# bbb_localization_cape.net
KiCad netlist of a schematic drawn in EAGLE
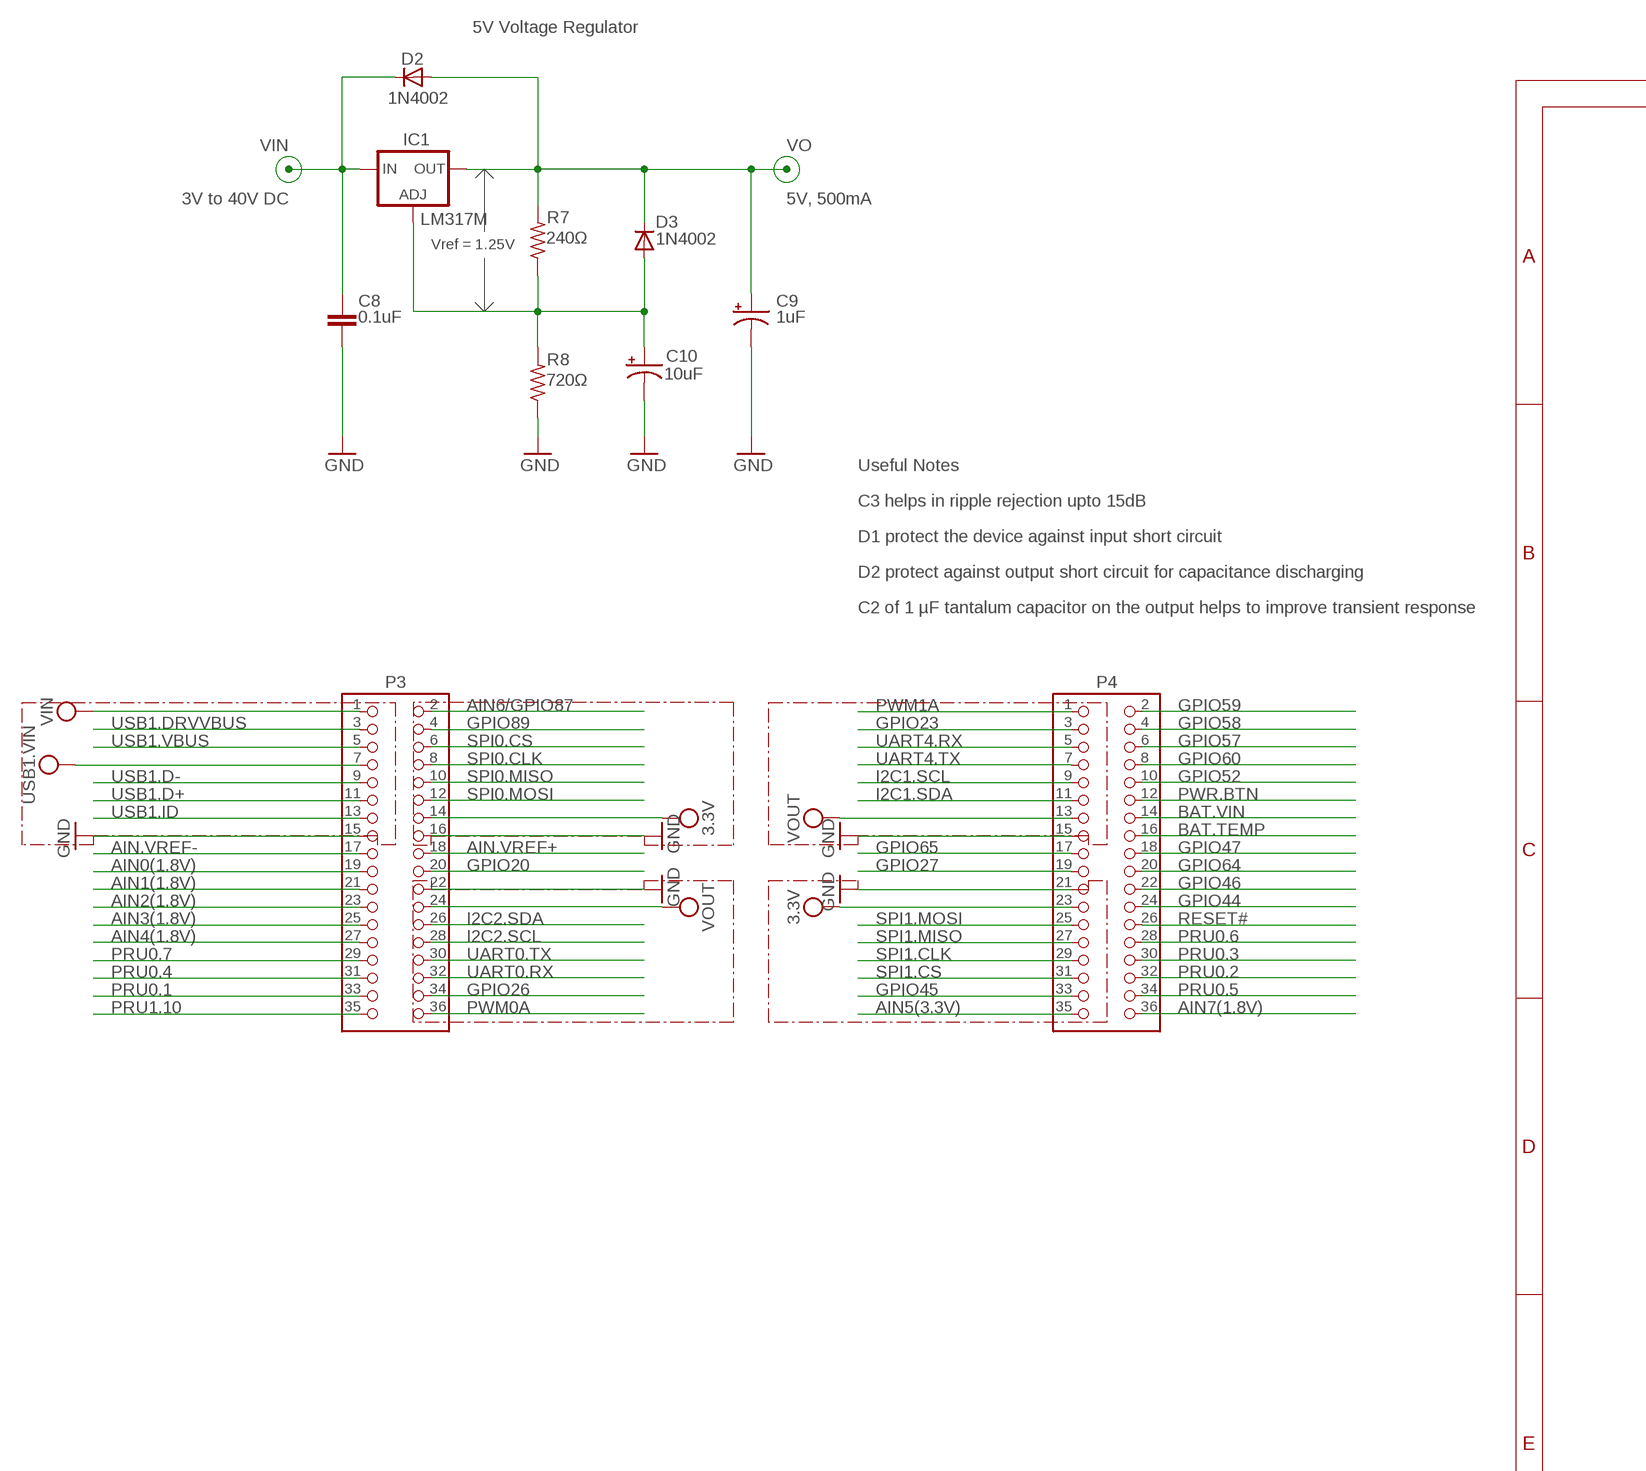
[diagram p0: schematic, sheet 1, part 1 of 2]
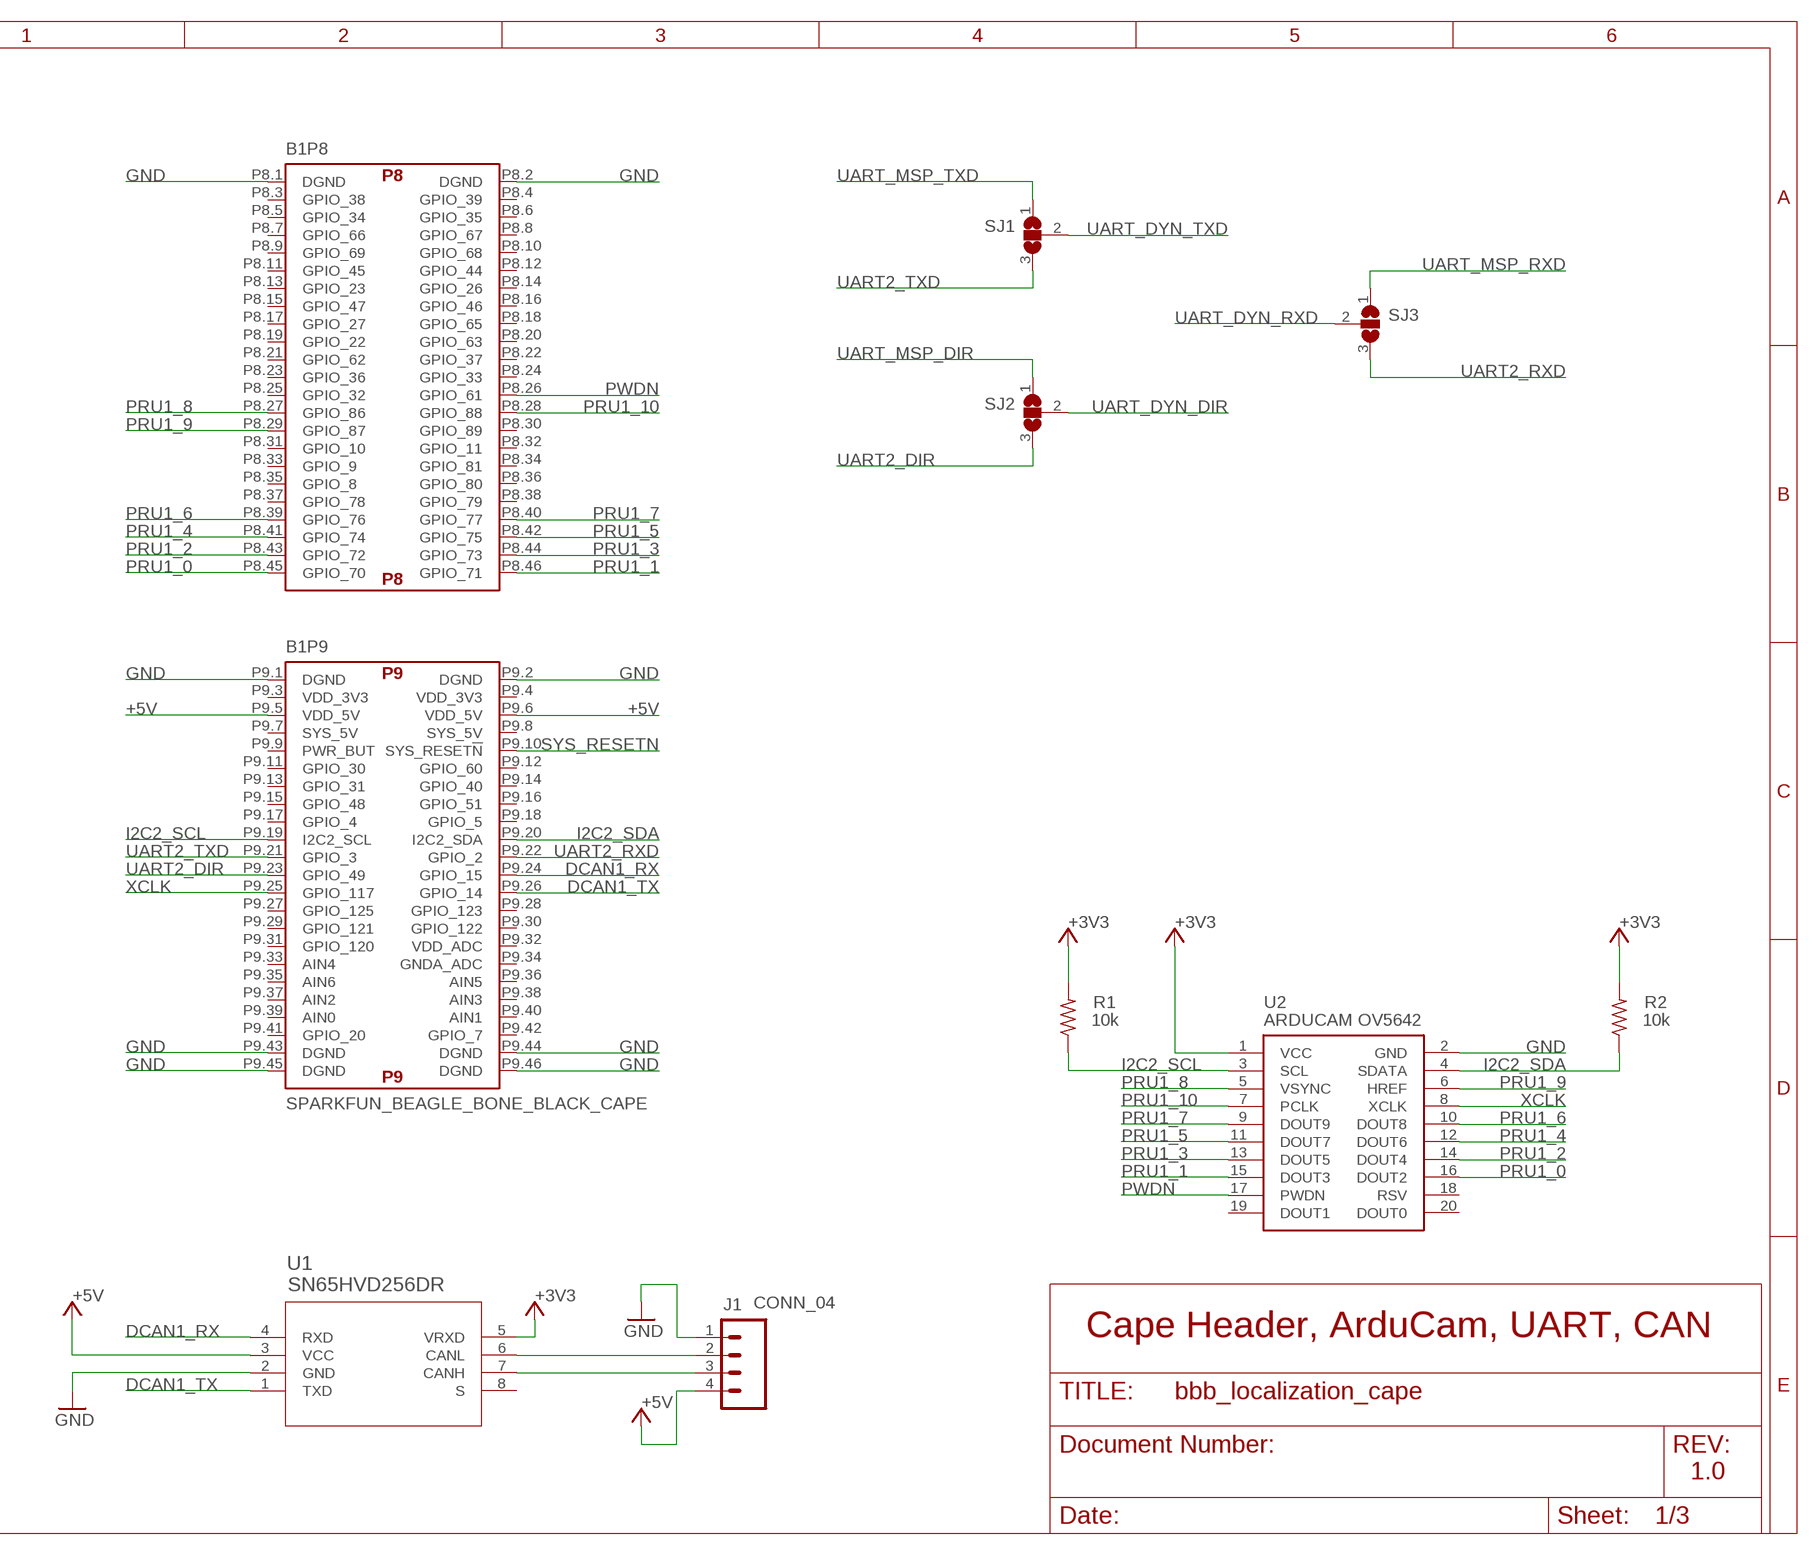
[diagram p1: schematic, sheet 1, part 2 of 2]
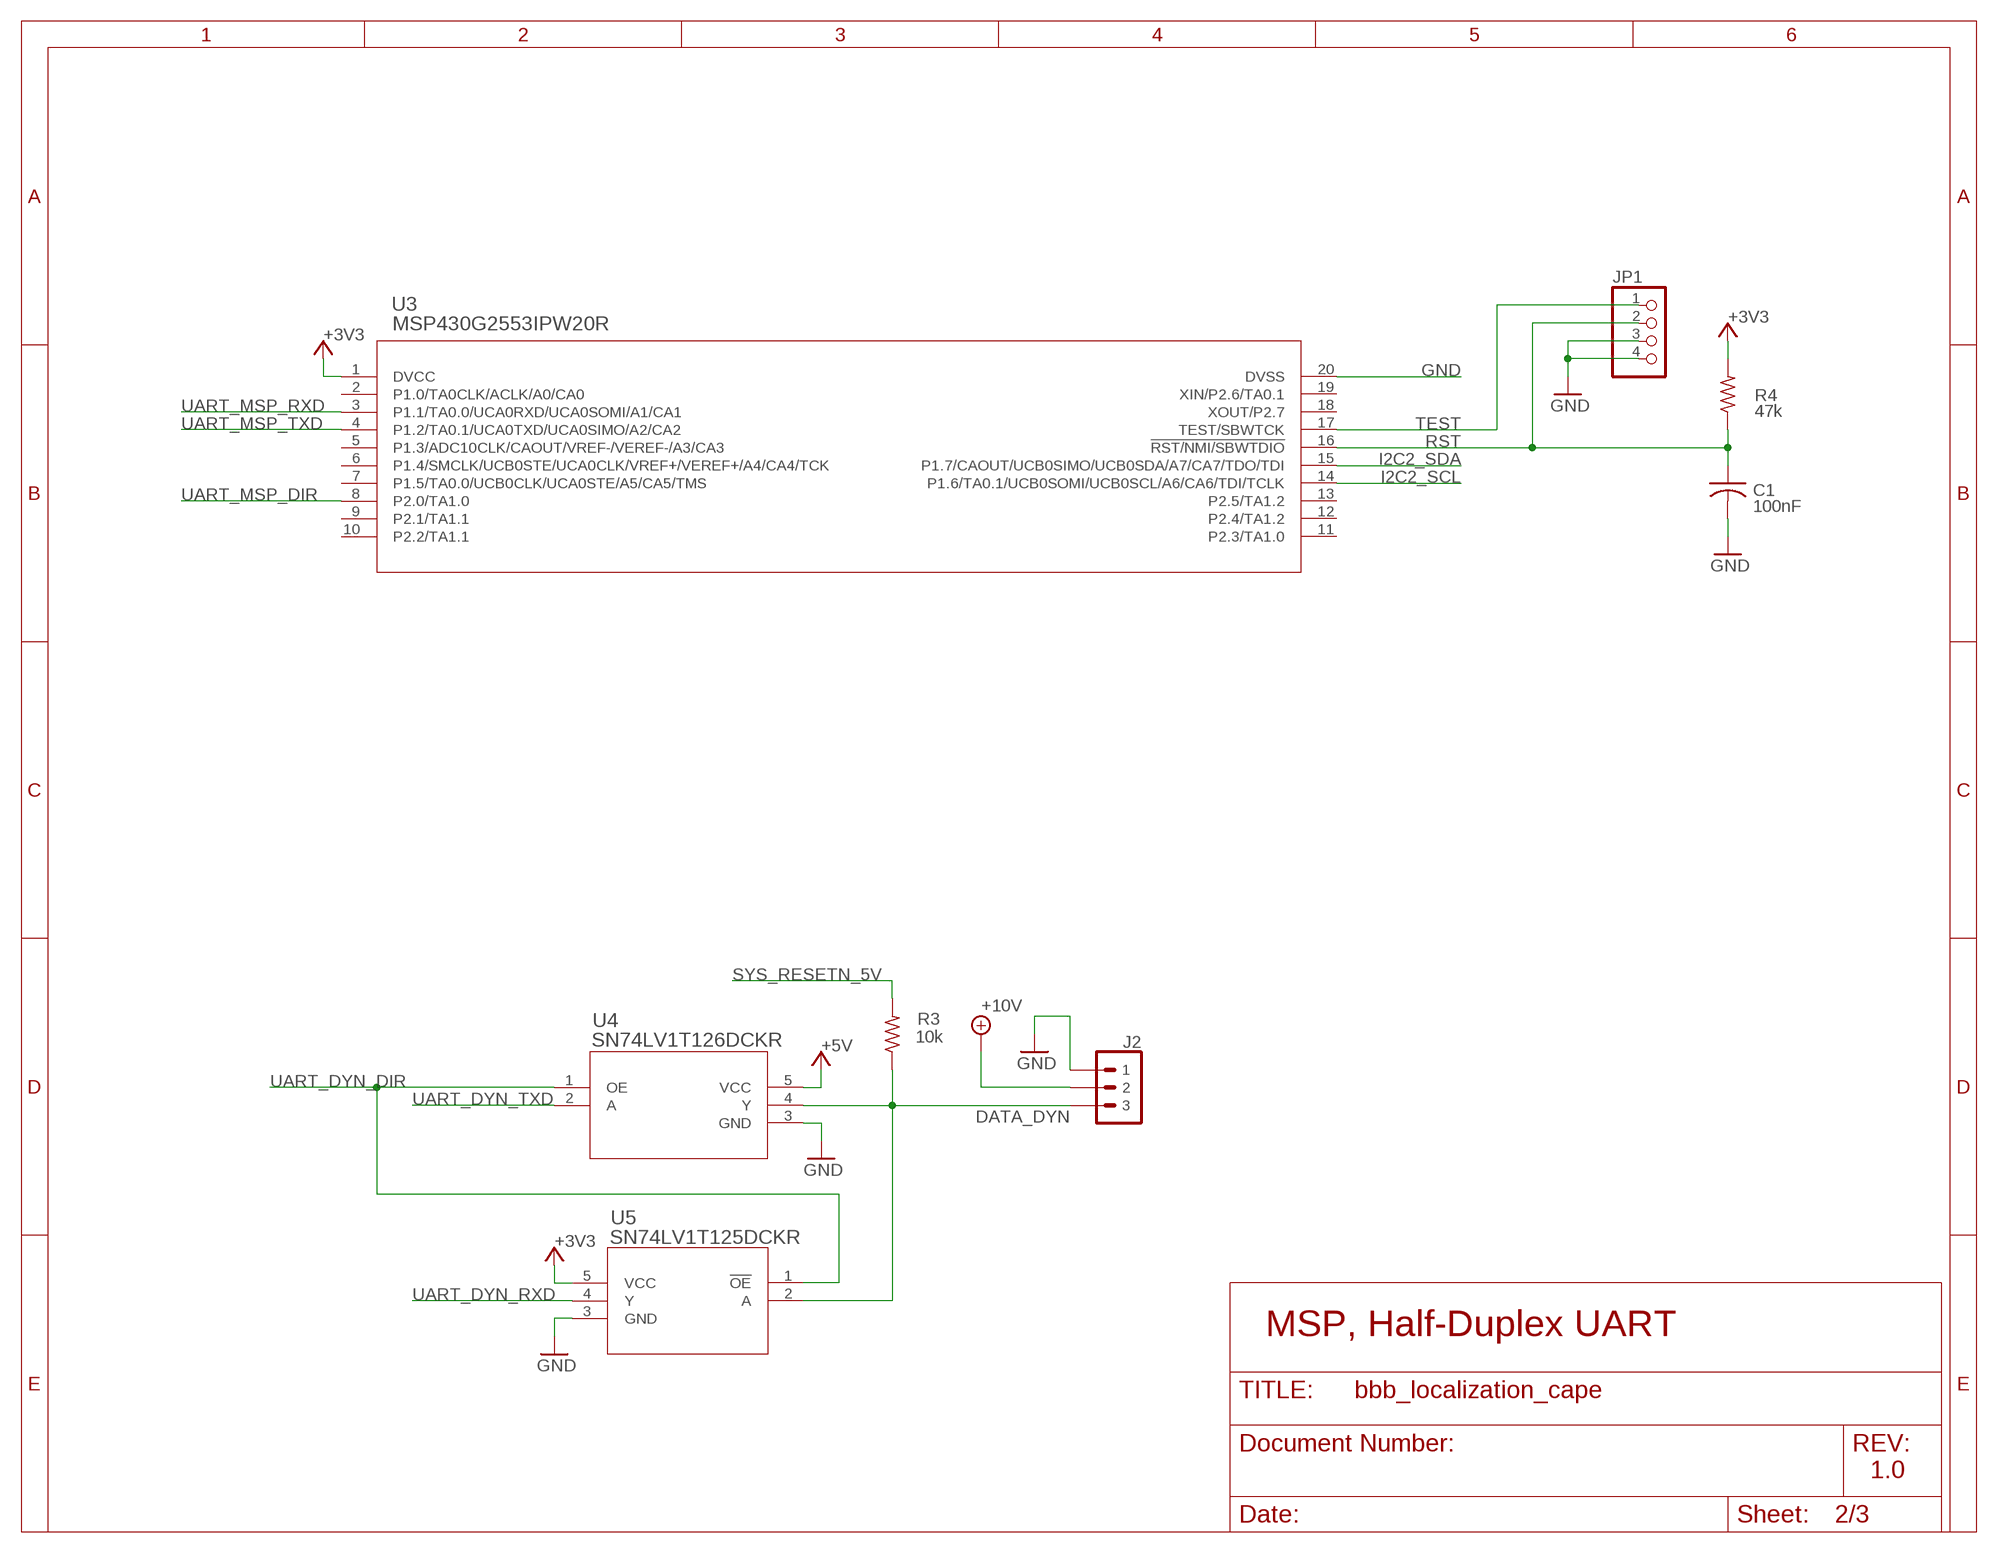
[diagram p2: schematic, sheet 2]
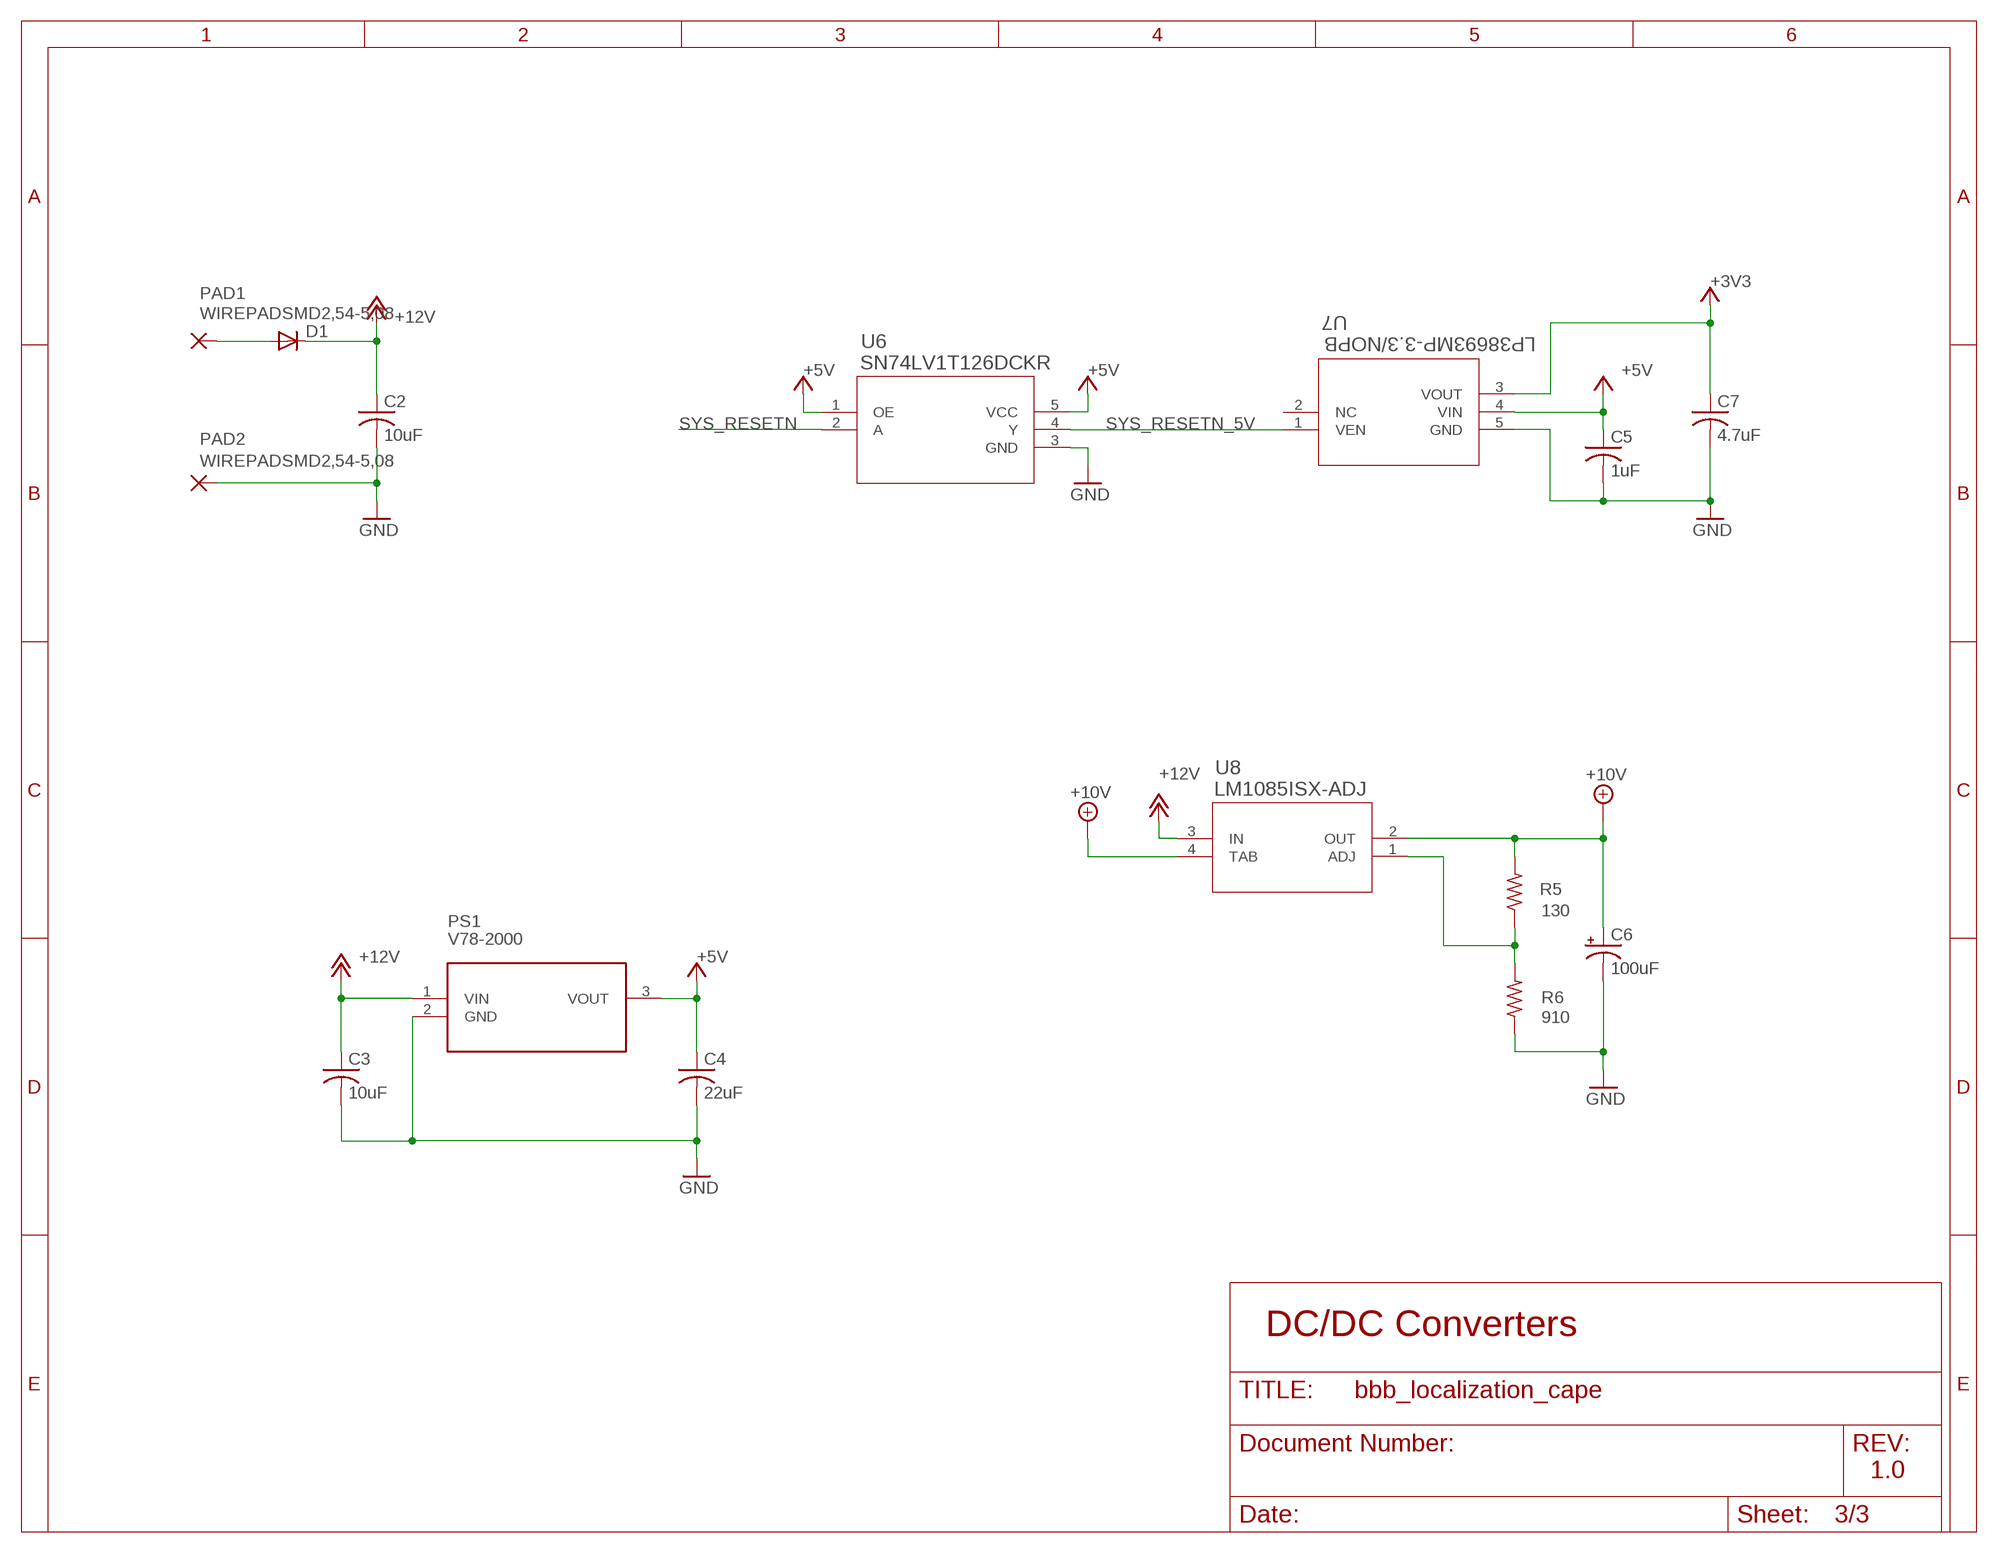
[diagram p3: schematic, sheet 3]

(export (version "E")
  (design (tool "Eeschema 10.0.6"))
  (components
    (comp (ref "C2")
      (value "10uF")
      (footprint "eagle-import:C0805")
      (fields
        (field (name "MANUFACTURER") "Murata Electronics North America")
        (field (name "MANUFACTURER_PART_NUMBER") "GRM21BR61E106MA73L")
      )
      (libsource (lib "eagle-import") (part "C-USC0805"))
    )
    (comp (ref "C3")
      (value "10uF")
      (footprint "eagle-import:C0805")
      (fields
        (field (name "MANUFACTURER") "Murata Electronics North America")
        (field (name "MANUFACTURER_PART_NUMBER") "GRM21BR61E106MA73L")
      )
      (libsource (lib "eagle-import") (part "C-USC0805"))
    )
    (comp (ref "C4")
      (value "22uF")
      (footprint "eagle-import:C0805")
      (fields
        (field (name "MANUFACTURER") "Samsung Electro-Mechanics America, Inc.")
        (field (name "MANUFACTURER_PART_NUMBER") "CL21A226MOCLRNC")
      )
      (libsource (lib "eagle-import") (part "C-USC0805"))
    )
    (comp (ref "C5")
      (value "1uF")
      (footprint "eagle-import:C0805")
      (fields
        (field (name "MANUFACTURER") "Samsung Electro-Mechanics America, Inc.")
        (field (name "MANUFACTURER_PART_NUMBER") "CL21B105KPFNNNE")
      )
      (libsource (lib "eagle-import") (part "C-USC0805"))
    )
    (comp (ref "C6")
      (value "100uF")
      (footprint "eagle-import:PANASONIC_E")
      (fields
        (field (name "MANUFACTURER") "TDK Corporation")
        (field (name "MANUFACTURER_PART_NUMBER") "C3216X5R1E476M160AC")
        (field (name "SPICEPREFIX") "C")
      )
      (libsource (lib "eagle-import") (part "CAPPANASONIC_E_"))
    )
    (comp (ref "C7")
      (value "4.7uF")
      (footprint "eagle-import:C0805")
      (fields
        (field (name "MANUFACTURER") "Samsung Electro-Mechanics America, Inc.")
        (field (name "MANUFACTURER_PART_NUMBER") "CL21A475KQFNNNG")
      )
      (libsource (lib "eagle-import") (part "C-USC0805"))
    )
    (comp (ref "D1")
      (value "DIODE-DO-214AC")
      (footprint "eagle-import:DO-214AC")
      (libsource (lib "eagle-import") (part "DIODE-DO-214AC"))
    )
    (comp (ref "PAD1")
      (value "WIREPADSMD2,54-5,08")
      (footprint "eagle-import:SMD2,54-5,08")
      (libsource (lib "eagle-import") (part "WIREPADSMD2,54-5,08"))
    )
    (comp (ref "PAD2")
      (value "WIREPADSMD2,54-5,08")
      (footprint "eagle-import:SMD2,54-5,08")
      (libsource (lib "eagle-import") (part "WIREPADSMD2,54-5,08"))
    )
    (comp (ref "PS1")
      (value "V78-2000")
      (footprint "eagle-import:V78-2000")
      (fields
        (field (name "MANUFACTURER") "CUI Inc.")
        (field (name "MANUFACTURER_PART_NUMBER") "V7805-2000R")
      )
      (libsource (lib "eagle-import") (part "V78-2000"))
    )
    (comp (ref "R5")
      (value "130")
      (footprint "eagle-import:R0805")
      (fields
        (field (name "MANUFACTURER") "Yageo")
        (field (name "MANUFACTURER_PART_NUMBER") "RC0805FR-07130RL")
      )
      (libsource (lib "eagle-import") (part "R-US_R0805"))
    )
    (comp (ref "R6")
      (value "910")
      (footprint "eagle-import:R0805")
      (fields
        (field (name "MANUFACTURER") "Yageo")
        (field (name "MANUFACTURER_PART_NUMBER") "RC0805FR-07910RL")
      )
      (libsource (lib "eagle-import") (part "R-US_R0805"))
    )
    (comp (ref "U6")
      (value "SN74LV1T126DCKR")
      (footprint "eagle-import:DCK5")
      (fields (field (name "MANUFACTURER") "Texas Instruments") (field (name "VENDOR") "Digi-Key"))
      (libsource (lib "eagle-import") (part "SN74LV1T126DCKR"))
    )
    (comp (ref "U7")
      (value "LP38693MP-3.3/NOPB")
      (footprint "eagle-import:MP05A")
      (fields
        (field (name "MANUFACTURER_PART_NUMBER") "LP38693MP3.3NOPB")
        (field (name "MANUFACTURER") "Texas Instruments")
        (field (name "MANUFACTURER_PART_NUMBER_1") "LP38693MP-3.3/NOPB")
        (field (name "VENDOR") "Digi-Key")
      )
      (libsource (lib "eagle-import") (part "LP38693MP-3.3/NOPB"))
    )
    (comp (ref "U8")
      (value "LM1085ISX-ADJ")
      (footprint "eagle-import:TS3B")
      (fields
        (field (name "MANUFACTURER_PART_NUMBER") "lm1085isxadj")
        (field (name "MANUFACTURER") "Texas Instruments")
        (field (name "MANUFACTURER_PART_NUMBER_1") "LM1085ISX-ADJ/NOPB")
        (field (name "VENDOR") "Digi-Key")
      )
      (libsource (lib "eagle-import") (part "LM1085ISX-ADJ"))
    )
    (comp (ref "C1")
      (value "100nF")
      (footprint "eagle-import:C0805")
      (fields
        (field (name "MANUFACTURER") "Samsung Electro-Mechanics America, Inc.")
        (field (name "MANUFACTURER_PART_NUMBER") "CL21B104KOANNNC")
      )
      (libsource (lib "eagle-import") (part "C-USC0805"))
    )
    (comp (ref "J2")
      (value "MOLEX-22-03-5035")
      (footprint "eagle-import:MOLEX-22-03-5035")
      (fields
        (field (name "MANUFACTURER") "Molex, LLC")
        (field (name "MANUFACTURER_PART_NUMBER") "22-03-5035")
      )
      (libsource (lib "eagle-import") (part "MOLEX-22-03-5035"))
    )
    (comp (ref "JP1")
      (value "PINHD-1X4")
      (footprint "eagle-import:1X04")
      (fields
        (field (name "MANUFACTURER") "Samtec Inc.")
        (field (name "MANUFACTURER_PART_NUMBER") "SSW-104-01-F-S")
      )
      (libsource (lib "eagle-import") (part "PINHD-1X4"))
    )
    (comp (ref "R3")
      (value "10k")
      (footprint "eagle-import:R0805")
      (fields
        (field (name "MANUFACTURER") "Yageo")
        (field (name "MANUFACTURER_PART_NUMBER") "RC0805JR-0710KL")
      )
      (libsource (lib "eagle-import") (part "R-US_R0805"))
    )
    (comp (ref "R4")
      (value "47k")
      (footprint "eagle-import:R0805")
      (fields
        (field (name "MANUFACTURER") "Stackpole Electronics Inc")
        (field (name "MANUFACTURER_PART_NUMBER") "RMCF0805JT47K0")
      )
      (libsource (lib "eagle-import") (part "R-US_R0805"))
    )
    (comp (ref "U3")
      (value "MSP430G2553IPW20R")
      (footprint "eagle-import:PW20")
      (fields (field (name "MANUFACTURER") "Texas Instruments") (field (name "VENDOR") "Digi-Key"))
      (libsource (lib "eagle-import") (part "MSP430G2553IPW20R"))
    )
    (comp (ref "U4")
      (value "SN74LV1T126DCKR")
      (footprint "eagle-import:DCK5")
      (fields (field (name "MANUFACTURER") "Texas Instruments") (field (name "VENDOR") "Digi-Key"))
      (libsource (lib "eagle-import") (part "SN74LV1T126DCKR"))
    )
    (comp (ref "U5")
      (value "SN74LV1T125DCKR")
      (footprint "eagle-import:DCK5")
      (fields (field (name "MANUFACTURER") "Texas Instruments") (field (name "VENDOR") "Digi-Key"))
      (libsource (lib "eagle-import") (part "SN74LV1T125DCKR"))
    )
    (comp (ref "B1")
      (value "SPARKFUN_BEAGLE_BONE_BLACK_CAPE")
      (footprint "eagle-import:BEAGLE_BONE_BLACK_CAPE")
      (libsource (lib "eagle-import") (part "SPARKFUN_BEAGLE_BONE_BLACK_CAPE"))
    )
    (comp (ref "C8")
      (value "0.1uF")
      (footprint "eagle-import:C075-052X106")
      (libsource (lib "eagle-import") (part "C-EU075-052X106"))
    )
    (comp (ref "C9")
      (value "1uF")
      (footprint "eagle-import:085CS_1AR")
      (libsource (lib "eagle-import") (part "CPOL-US085CS-1AR"))
    )
    (comp (ref "C10")
      (value "10uF")
      (footprint "eagle-import:085CS_1AR")
      (libsource (lib "eagle-import") (part "CPOL-US085CS-1AR"))
    )
    (comp (ref "D2")
      (value "1N4002")
      (footprint "eagle-import:DO41-10")
      (libsource (lib "eagle-import") (part "1N4004"))
    )
    (comp (ref "D3")
      (value "1N4002")
      (footprint "eagle-import:DO41-10")
      (libsource (lib "eagle-import") (part "1N4004"))
    )
    (comp (ref "IC1")
      (value "LM317MBSTT3")
      (footprint "eagle-import:SOT223")
      (fields (field (name "PARTNUMBER") "LM317M"))
      (libsource (lib "eagle-import") (part "LM317?MBSTT3"))
    )
    (comp (ref "J1")
      (value "CONN_04")
      (footprint "eagle-import:JST-4-PTH-VERT")
      (fields
        (field (name "MANUFACTURER") "JST Sales America Inc.")
        (field (name "MANUFACTURER_PART_NUMBER") "B4B-PH-K-S(LF)(SN)")
      )
      (libsource (lib "eagle-import") (part "CONN_04"))
    )
    (comp (ref "P3")
      (value "2X18-(INCH)-0.1-TH-(35MIL-DIA)-W/O-SILK")
      (footprint "eagle-import:TH-2X18-(35MIL-DIA)-W_O-SILK")
      (libsource (lib "eagle-import") (part "2X18-(INCH)-0.1-TH-(35MIL-DIA)-W/O-SILK"))
    )
    (comp (ref "P4")
      (value "2X18-(INCH)-0.1-TH-(35MIL-DIA)-W/O-SILK")
      (footprint "eagle-import:TH-2X18-(35MIL-DIA)-W_O-SILK")
      (libsource (lib "eagle-import") (part "2X18-(INCH)-0.1-TH-(35MIL-DIA)-W/O-SILK"))
    )
    (comp (ref "R1")
      (value "10k")
      (footprint "eagle-import:R0805")
      (fields
        (field (name "MANUFACTURER") "Yageo")
        (field (name "MANUFACTURER_PART_NUMBER") "RC0805JR-0710KL")
      )
      (libsource (lib "eagle-import") (part "R-US_R0805"))
    )
    (comp (ref "R2")
      (value "10k")
      (footprint "eagle-import:R0805")
      (fields
        (field (name "MANUFACTURER") "Yageo")
        (field (name "MANUFACTURER_PART_NUMBER") "RC0805JR-0710KL")
      )
      (libsource (lib "eagle-import") (part "R-US_R0805"))
    )
    (comp (ref "R7")
      (value "240Ω")
      (footprint "eagle-import:M0805")
      (libsource (lib "eagle-import") (part "resistor_R-US_M0805"))
    )
    (comp (ref "R8")
      (value "720Ω")
      (footprint "eagle-import:M0805")
      (libsource (lib "eagle-import") (part "resistor_R-US_M0805"))
    )
    (comp (ref "SJ1")
      (value "SJ2W")
      (footprint "eagle-import:SJ_2")
      (libsource (lib "eagle-import") (part "SJ2W"))
    )
    (comp (ref "SJ2")
      (value "SJ2W")
      (footprint "eagle-import:SJ_2")
      (libsource (lib "eagle-import") (part "SJ2W"))
    )
    (comp (ref "SJ3")
      (value "SJ2W")
      (footprint "eagle-import:SJ_2")
      (libsource (lib "eagle-import") (part "SJ2W"))
    )
    (comp (ref "U1")
      (value "SN65HVD256DR")
      (footprint "eagle-import:D8")
      (fields (field (name "MANUFACTURER") "Texas Instruments") (field (name "VENDOR") "Digi-Key"))
      (libsource (lib "eagle-import") (part "SN65HVD256DR"))
    )
    (comp (ref "U2")
      (value "ARDUCAMOV5642")
      (footprint "eagle-import:ARDUCAM")
      (fields
        (field (name "MANUFACTURER") "Samtec Inc.")
        (field (name "MANUFACTURER_PART_NUMBER") "SSW-110-02-L-D")
      )
      (libsource (lib "eagle-import") (part "ARDUCAMOV5642"))
    )
  )
  (nets
    (net (code "1") (name "+3V3") (class "Default")
      (node (ref "C7") (pin "1") (pinfunction "1_1") (pintype "passive"))
      (node (ref "R1") (pin "2") (pinfunction "2_2") (pintype "passive"))
      (node (ref "R2") (pin "2") (pinfunction "2_2") (pintype "passive"))
      (node (ref "R4") (pin "2") (pinfunction "2_2") (pintype "passive"))
      (node (ref "U1") (pin "5") (pinfunction "VRXD_5") (pintype "power_in"))
      (node (ref "U2") (pin "1") (pinfunction "VCC_1") (pintype "bidirectional"))
      (node (ref "U3") (pin "1") (pinfunction "DVCC_1") (pintype "power_in"))
      (node (ref "U5") (pin "5") (pinfunction "VCC_5") (pintype "power_in"))
      (node (ref "U7") (pin "3") (pinfunction "VOUT_3") (pintype "output"))
    )
    (net (code "2") (name "+5V") (class "Default")
      (node (ref "B1") (pin "P9.5") (pinfunction "VDD_5V_P9.5") (pintype "bidirectional"))
      (node (ref "B1") (pin "P9.6") (pinfunction "VDD_5V_P9.6") (pintype "bidirectional"))
      (node (ref "C4") (pin "1") (pinfunction "1_1") (pintype "passive"))
      (node (ref "C5") (pin "1") (pinfunction "1_1") (pintype "passive"))
      (node (ref "J1") (pin "4") (pinfunction "4_4") (pintype "passive"))
      (node (ref "PS1") (pin "3") (pinfunction "VOUT_3") (pintype "bidirectional"))
      (node (ref "U1") (pin "3") (pinfunction "VCC_3") (pintype "power_in"))
      (node (ref "U4") (pin "5") (pinfunction "VCC_5") (pintype "power_in"))
      (node (ref "U6") (pin "1") (pinfunction "OE_1") (pintype "input"))
      (node (ref "U6") (pin "5") (pinfunction "VCC_5") (pintype "power_in"))
      (node (ref "U7") (pin "4") (pinfunction "VIN_4") (pintype "input"))
    )
    (net (code "3") (name "+10V") (class "Default")
      (node (ref "C6") (pin "+") (pinfunction "+_+") (pintype "passive"))
      (node (ref "J2") (pin "P$2") (pinfunction "2_P$2") (pintype "bidirectional"))
      (node (ref "R5") (pin "2") (pinfunction "2_2") (pintype "passive"))
      (node (ref "U8") (pin "2") (pinfunction "OUT_2") (pintype "power_in"))
      (node (ref "U8") (pin "4") (pinfunction "TAB_4") (pintype "power_in"))
    )
    (net (code "4") (name "+12V") (class "Default")
      (node (ref "C2") (pin "1") (pinfunction "1_1") (pintype "passive"))
      (node (ref "C3") (pin "1") (pinfunction "1_1") (pintype "passive"))
      (node (ref "D1") (pin "C") (pinfunction "C_C") (pintype "passive"))
      (node (ref "PS1") (pin "1") (pinfunction "VIN_1") (pintype "bidirectional"))
      (node (ref "U8") (pin "3") (pinfunction "IN_3") (pintype "power_in"))
    )
    (net (code "5") (name "3.3V") (class "Default")
      (node (ref "P3") (pin "14") (pinfunction "14_14") (pintype "bidirectional"))
      (node (ref "P4") (pin "23") (pinfunction "23_23") (pintype "bidirectional"))
    )
    (net (code "6") (name "AIN.VREF+") (class "Default")
      (node (ref "P3") (pin "18") (pinfunction "18_18") (pintype "bidirectional"))
    )
    (net (code "7") (name "AIN.VREF-") (class "Default")
      (node (ref "P3") (pin "17") (pinfunction "17_17") (pintype "bidirectional"))
    )
    (net (code "8") (name "AIN0(1.8V)") (class "Default")
      (node (ref "P3") (pin "19") (pinfunction "19_19") (pintype "bidirectional"))
    )
    (net (code "9") (name "AIN1(1.8V)") (class "Default")
      (node (ref "P3") (pin "21") (pinfunction "21_21") (pintype "bidirectional"))
    )
    (net (code "10") (name "AIN2(1.8V)") (class "Default")
      (node (ref "P3") (pin "23") (pinfunction "23_23") (pintype "bidirectional"))
    )
    (net (code "11") (name "AIN3(1.8V)") (class "Default")
      (node (ref "P3") (pin "25") (pinfunction "25_25") (pintype "bidirectional"))
    )
    (net (code "12") (name "AIN4(1.8V)") (class "Default")
      (node (ref "P3") (pin "27") (pinfunction "27_27") (pintype "bidirectional"))
    )
    (net (code "13") (name "AIN5(3.3V)") (class "Default")
      (node (ref "P4") (pin "35") (pinfunction "35_35") (pintype "bidirectional"))
    )
    (net (code "14") (name "AIN6{slash}GPIO87") (class "Default")
      (node (ref "P3") (pin "2") (pinfunction "2_2") (pintype "bidirectional"))
    )
    (net (code "15") (name "AIN7(1.8V)") (class "Default")
      (node (ref "P4") (pin "36") (pinfunction "36_36") (pintype "bidirectional"))
    )
    (net (code "16") (name "BAT.TEMP") (class "Default")
      (node (ref "P4") (pin "16") (pinfunction "16_16") (pintype "bidirectional"))
    )
    (net (code "17") (name "BAT.VIN") (class "Default")
      (node (ref "P4") (pin "14") (pinfunction "14_14") (pintype "bidirectional"))
    )
    (net (code "18") (name "DATA_DYN") (class "Default")
      (node (ref "J2") (pin "P$3") (pinfunction "3_P$3") (pintype "bidirectional"))
      (node (ref "R3") (pin "1") (pinfunction "1_1") (pintype "passive"))
      (node (ref "U4") (pin "4") (pinfunction "Y_4") (pintype "output"))
      (node (ref "U5") (pin "2") (pinfunction "A_2") (pintype "input"))
    )
    (net (code "19") (name "DCAN1_RX") (class "Default")
      (node (ref "B1") (pin "P9.24") (pinfunction "GPIO_15_P9.24") (pintype "bidirectional"))
      (node (ref "U1") (pin "4") (pinfunction "RXD_4") (pintype "output"))
    )
    (net (code "20") (name "DCAN1_TX") (class "Default")
      (node (ref "B1") (pin "P9.26") (pinfunction "GPIO_14_P9.26") (pintype "bidirectional"))
      (node (ref "U1") (pin "1") (pinfunction "TXD_1") (pintype "input"))
    )
    (net (code "21") (name "GND") (class "Default")
      (node (ref "B1") (pin "P8.1") (pinfunction "DGND_P8.1") (pintype "bidirectional"))
      (node (ref "B1") (pin "P8.2") (pinfunction "DGND_P8.2") (pintype "bidirectional"))
      (node (ref "B1") (pin "P9.1") (pinfunction "DGND_P9.1") (pintype "bidirectional"))
      (node (ref "B1") (pin "P9.2") (pinfunction "DGND_P9.2") (pintype "bidirectional"))
      (node (ref "B1") (pin "P9.43") (pinfunction "DGND_P9.43") (pintype "bidirectional"))
      (node (ref "B1") (pin "P9.44") (pinfunction "DGND_P9.44") (pintype "bidirectional"))
      (node (ref "B1") (pin "P9.45") (pinfunction "DGND_P9.45") (pintype "bidirectional"))
      (node (ref "B1") (pin "P9.46") (pinfunction "DGND_P9.46") (pintype "bidirectional"))
      (node (ref "C1") (pin "2") (pinfunction "2_2") (pintype "passive"))
      (node (ref "C10") (pin "-") (pinfunction "-_-") (pintype "passive"))
      (node (ref "C2") (pin "2") (pinfunction "2_2") (pintype "passive"))
      (node (ref "C3") (pin "2") (pinfunction "2_2") (pintype "passive"))
      (node (ref "C4") (pin "2") (pinfunction "2_2") (pintype "passive"))
      (node (ref "C5") (pin "2") (pinfunction "2_2") (pintype "passive"))
      (node (ref "C6") (pin "-") (pinfunction "-_-") (pintype "passive"))
      (node (ref "C7") (pin "2") (pinfunction "2_2") (pintype "passive"))
      (node (ref "C8") (pin "2") (pinfunction "2_2") (pintype "passive"))
      (node (ref "C9") (pin "-") (pinfunction "-_-") (pintype "passive"))
      (node (ref "J1") (pin "1") (pinfunction "1_1") (pintype "passive"))
      (node (ref "J2") (pin "P$1") (pinfunction "1_P$1") (pintype "bidirectional"))
      (node (ref "JP1") (pin "3") (pinfunction "3_3") (pintype "passive"))
      (node (ref "JP1") (pin "4") (pinfunction "4_4") (pintype "passive"))
      (node (ref "P3") (pin "15") (pinfunction "15_15") (pintype "bidirectional"))
      (node (ref "P3") (pin "16") (pinfunction "16_16") (pintype "bidirectional"))
      (node (ref "P3") (pin "22") (pinfunction "22_22") (pintype "bidirectional"))
      (node (ref "P4") (pin "15") (pinfunction "15_15") (pintype "bidirectional"))
      (node (ref "P4") (pin "21") (pinfunction "21_21") (pintype "bidirectional"))
      (node (ref "PAD2") (pin "1") (pinfunction "P_1") (pintype "passive"))
      (node (ref "PS1") (pin "2") (pinfunction "GND_2") (pintype "bidirectional"))
      (node (ref "R6") (pin "1") (pinfunction "1_1") (pintype "passive"))
      (node (ref "R8") (pin "1") (pinfunction "1_1") (pintype "passive"))
      (node (ref "U1") (pin "2") (pinfunction "GND_2") (pintype "power_in"))
      (node (ref "U2") (pin "2") (pinfunction "GND_2") (pintype "bidirectional"))
      (node (ref "U3") (pin "20") (pinfunction "DVSS_20") (pintype "power_in"))
      (node (ref "U4") (pin "3") (pinfunction "GND_3") (pintype "power_in"))
      (node (ref "U5") (pin "3") (pinfunction "GND_3") (pintype "power_in"))
      (node (ref "U6") (pin "3") (pinfunction "GND_3") (pintype "power_in"))
      (node (ref "U7") (pin "5") (pinfunction "GND_5") (pintype "passive"))
    )
    (net (code "22") (name "GPIO20") (class "Default")
      (node (ref "P3") (pin "20") (pinfunction "20_20") (pintype "bidirectional"))
    )
    (net (code "23") (name "GPIO23") (class "Default")
      (node (ref "P4") (pin "3") (pinfunction "3_3") (pintype "bidirectional"))
    )
    (net (code "24") (name "GPIO26") (class "Default")
      (node (ref "P3") (pin "34") (pinfunction "34_34") (pintype "bidirectional"))
    )
    (net (code "25") (name "GPIO27") (class "Default")
      (node (ref "P4") (pin "19") (pinfunction "19_19") (pintype "bidirectional"))
    )
    (net (code "26") (name "GPIO44") (class "Default")
      (node (ref "P4") (pin "24") (pinfunction "24_24") (pintype "bidirectional"))
    )
    (net (code "27") (name "GPIO45") (class "Default")
      (node (ref "P4") (pin "33") (pinfunction "33_33") (pintype "bidirectional"))
    )
    (net (code "28") (name "GPIO46") (class "Default")
      (node (ref "P4") (pin "22") (pinfunction "22_22") (pintype "bidirectional"))
    )
    (net (code "29") (name "GPIO47") (class "Default")
      (node (ref "P4") (pin "18") (pinfunction "18_18") (pintype "bidirectional"))
    )
    (net (code "30") (name "GPIO52") (class "Default")
      (node (ref "P4") (pin "10") (pinfunction "10_10") (pintype "bidirectional"))
    )
    (net (code "31") (name "GPIO57") (class "Default")
      (node (ref "P4") (pin "6") (pinfunction "6_6") (pintype "bidirectional"))
    )
    (net (code "32") (name "GPIO58") (class "Default")
      (node (ref "P4") (pin "4") (pinfunction "4_4") (pintype "bidirectional"))
    )
    (net (code "33") (name "GPIO59") (class "Default")
      (node (ref "P4") (pin "2") (pinfunction "2_2") (pintype "bidirectional"))
    )
    (net (code "34") (name "GPIO60") (class "Default")
      (node (ref "P4") (pin "8") (pinfunction "8_8") (pintype "bidirectional"))
    )
    (net (code "35") (name "GPIO64") (class "Default")
      (node (ref "P4") (pin "20") (pinfunction "20_20") (pintype "bidirectional"))
    )
    (net (code "36") (name "GPIO65") (class "Default")
      (node (ref "P4") (pin "17") (pinfunction "17_17") (pintype "bidirectional"))
    )
    (net (code "37") (name "GPIO89") (class "Default")
      (node (ref "P3") (pin "4") (pinfunction "4_4") (pintype "bidirectional"))
    )
    (net (code "38") (name "I2C1.SCL") (class "Default")
      (node (ref "P4") (pin "9") (pinfunction "9_9") (pintype "bidirectional"))
    )
    (net (code "39") (name "I2C1.SDA") (class "Default")
      (node (ref "P4") (pin "11") (pinfunction "11_11") (pintype "bidirectional"))
    )
    (net (code "40") (name "I2C2.SCL") (class "Default")
      (node (ref "P3") (pin "28") (pinfunction "28_28") (pintype "bidirectional"))
    )
    (net (code "41") (name "I2C2.SDA") (class "Default")
      (node (ref "P3") (pin "26") (pinfunction "26_26") (pintype "bidirectional"))
    )
    (net (code "42") (name "I2C2_SCL") (class "Default")
      (node (ref "B1") (pin "P9.19") (pinfunction "I2C2_SCL_P9.19") (pintype "bidirectional"))
      (node (ref "R1") (pin "1") (pinfunction "1_1") (pintype "passive"))
      (node (ref "U2") (pin "3") (pinfunction "SCL_3") (pintype "bidirectional"))
      (node (ref "U3") (pin "14") (pinfunction "P1.6/TA0.1/UCB0SOMI/UCB0SCL/A6/CA6/TDI/TCLK_14") (pintype "bidirectional"))
    )
    (net (code "43") (name "I2C2_SDA") (class "Default")
      (node (ref "B1") (pin "P9.20") (pinfunction "I2C2_SDA_P9.20") (pintype "bidirectional"))
      (node (ref "R2") (pin "1") (pinfunction "1_1") (pintype "passive"))
      (node (ref "U2") (pin "4") (pinfunction "SDATA_4") (pintype "bidirectional"))
      (node (ref "U3") (pin "15") (pinfunction "P1.7/CAOUT/UCB0SIMO/UCB0SDA/A7/CA7/TDO/TDI_15") (pintype "bidirectional"))
    )
    (net (code "44") (name "Net-(IC1-ADJ)") (class "Default")
      (node (ref "C10") (pin "+") (pinfunction "+_+") (pintype "passive"))
      (node (ref "D3") (pin "A") (pinfunction "A_A") (pintype "passive"))
      (node (ref "IC1") (pin "1") (pinfunction "ADJ_1") (pintype "input"))
      (node (ref "R7") (pin "1") (pinfunction "1_1") (pintype "passive"))
      (node (ref "R8") (pin "2") (pinfunction "2_2") (pintype "passive"))
    )
    (net (code "45") (name "Net-(PAD1-P)") (class "Default")
      (node (ref "D1") (pin "A") (pinfunction "A_A") (pintype "passive"))
      (node (ref "PAD1") (pin "1") (pinfunction "P_1") (pintype "passive"))
    )
    (net (code "46") (name "Net-(U1-CANH)") (class "Default")
      (node (ref "J1") (pin "3") (pinfunction "3_3") (pintype "passive"))
      (node (ref "U1") (pin "7") (pinfunction "CANH_7") (pintype "output"))
    )
    (net (code "47") (name "Net-(U1-CANL)") (class "Default")
      (node (ref "J1") (pin "2") (pinfunction "2_2") (pintype "passive"))
      (node (ref "U1") (pin "6") (pinfunction "CANL_6") (pintype "output"))
    )
    (net (code "48") (name "Net-(U8-ADJ)") (class "Default")
      (node (ref "R5") (pin "1") (pinfunction "1_1") (pintype "passive"))
      (node (ref "R6") (pin "2") (pinfunction "2_2") (pintype "passive"))
      (node (ref "U8") (pin "1") (pinfunction "ADJ_1") (pintype "input"))
    )
    (net (code "49") (name "PRU0.1") (class "Default")
      (node (ref "P3") (pin "33") (pinfunction "33_33") (pintype "bidirectional"))
    )
    (net (code "50") (name "PRU0.2") (class "Default")
      (node (ref "P4") (pin "32") (pinfunction "32_32") (pintype "bidirectional"))
    )
    (net (code "51") (name "PRU0.3") (class "Default")
      (node (ref "P4") (pin "30") (pinfunction "30_30") (pintype "bidirectional"))
    )
    (net (code "52") (name "PRU0.4") (class "Default")
      (node (ref "P3") (pin "31") (pinfunction "31_31") (pintype "bidirectional"))
    )
    (net (code "53") (name "PRU0.5") (class "Default")
      (node (ref "P4") (pin "34") (pinfunction "34_34") (pintype "bidirectional"))
    )
    (net (code "54") (name "PRU0.6") (class "Default")
      (node (ref "P4") (pin "28") (pinfunction "28_28") (pintype "bidirectional"))
    )
    (net (code "55") (name "PRU0.7") (class "Default")
      (node (ref "P3") (pin "29") (pinfunction "29_29") (pintype "bidirectional"))
    )
    (net (code "56") (name "PRU1.10") (class "Default")
      (node (ref "P3") (pin "35") (pinfunction "35_35") (pintype "bidirectional"))
    )
    (net (code "57") (name "PRU1_0") (class "Default")
      (node (ref "B1") (pin "P8.45") (pinfunction "GPIO_70_P8.45") (pintype "bidirectional"))
      (node (ref "U2") (pin "16") (pinfunction "DOUT2_16") (pintype "bidirectional"))
    )
    (net (code "58") (name "PRU1_1") (class "Default")
      (node (ref "B1") (pin "P8.46") (pinfunction "GPIO_71_P8.46") (pintype "bidirectional"))
      (node (ref "U2") (pin "15") (pinfunction "DOUT3_15") (pintype "bidirectional"))
    )
    (net (code "59") (name "PRU1_2") (class "Default")
      (node (ref "B1") (pin "P8.43") (pinfunction "GPIO_72_P8.43") (pintype "bidirectional"))
      (node (ref "U2") (pin "14") (pinfunction "DOUT4_14") (pintype "bidirectional"))
    )
    (net (code "60") (name "PRU1_3") (class "Default")
      (node (ref "B1") (pin "P8.44") (pinfunction "GPIO_73_P8.44") (pintype "bidirectional"))
      (node (ref "U2") (pin "13") (pinfunction "DOUT5_13") (pintype "bidirectional"))
    )
    (net (code "61") (name "PRU1_4") (class "Default")
      (node (ref "B1") (pin "P8.41") (pinfunction "GPIO_74_P8.41") (pintype "bidirectional"))
      (node (ref "U2") (pin "12") (pinfunction "DOUT6_12") (pintype "bidirectional"))
    )
    (net (code "62") (name "PRU1_5") (class "Default")
      (node (ref "B1") (pin "P8.42") (pinfunction "GPIO_75_P8.42") (pintype "bidirectional"))
      (node (ref "U2") (pin "11") (pinfunction "DOUT7_11") (pintype "bidirectional"))
    )
    (net (code "63") (name "PRU1_6") (class "Default")
      (node (ref "B1") (pin "P8.39") (pinfunction "GPIO_76_P8.39") (pintype "bidirectional"))
      (node (ref "U2") (pin "10") (pinfunction "DOUT8_10") (pintype "bidirectional"))
    )
    (net (code "64") (name "PRU1_7") (class "Default")
      (node (ref "B1") (pin "P8.40") (pinfunction "GPIO_77_P8.40") (pintype "bidirectional"))
      (node (ref "U2") (pin "9") (pinfunction "DOUT9_9") (pintype "bidirectional"))
    )
    (net (code "65") (name "PRU1_8") (class "Default")
      (node (ref "B1") (pin "P8.27") (pinfunction "GPIO_86_P8.27") (pintype "bidirectional"))
      (node (ref "U2") (pin "5") (pinfunction "VSYNC_5") (pintype "bidirectional"))
    )
    (net (code "66") (name "PRU1_9") (class "Default")
      (node (ref "B1") (pin "P8.29") (pinfunction "GPIO_87_P8.29") (pintype "bidirectional"))
      (node (ref "U2") (pin "6") (pinfunction "HREF_6") (pintype "bidirectional"))
    )
    (net (code "67") (name "PRU1_10") (class "Default")
      (node (ref "B1") (pin "P8.28") (pinfunction "GPIO_88_P8.28") (pintype "bidirectional"))
      (node (ref "U2") (pin "7") (pinfunction "PCLK_7") (pintype "bidirectional"))
    )
    (net (code "68") (name "PWDN") (class "Default")
      (node (ref "B1") (pin "P8.26") (pinfunction "GPIO_61_P8.26") (pintype "bidirectional"))
      (node (ref "U2") (pin "17") (pinfunction "PWDN_17") (pintype "bidirectional"))
    )
    (net (code "69") (name "PWM0A") (class "Default")
      (node (ref "P3") (pin "36") (pinfunction "36_36") (pintype "bidirectional"))
    )
    (net (code "70") (name "PWM1A") (class "Default")
      (node (ref "P4") (pin "1") (pinfunction "1_1") (pintype "bidirectional"))
    )
    (net (code "71") (name "PWR.BTN") (class "Default")
      (node (ref "P4") (pin "12") (pinfunction "12_12") (pintype "bidirectional"))
    )
    (net (code "72") (name "RESET#") (class "Default")
      (node (ref "P4") (pin "26") (pinfunction "26_26") (pintype "bidirectional"))
    )
    (net (code "73") (name "RST") (class "Default")
      (node (ref "C1") (pin "1") (pinfunction "1_1") (pintype "passive"))
      (node (ref "JP1") (pin "2") (pinfunction "2_2") (pintype "passive"))
      (node (ref "R4") (pin "1") (pinfunction "1_1") (pintype "passive"))
      (node (ref "U3") (pin "16") (pinfunction "~{RST/NMI/SBWTDIO}_16") (pintype "bidirectional"))
    )
    (net (code "74") (name "SPI0.CLK") (class "Default")
      (node (ref "P3") (pin "8") (pinfunction "8_8") (pintype "bidirectional"))
    )
    (net (code "75") (name "SPI0.CS") (class "Default")
      (node (ref "P3") (pin "6") (pinfunction "6_6") (pintype "bidirectional"))
    )
    (net (code "76") (name "SPI0.MISO") (class "Default")
      (node (ref "P3") (pin "10") (pinfunction "10_10") (pintype "bidirectional"))
    )
    (net (code "77") (name "SPI0.MOSI") (class "Default")
      (node (ref "P3") (pin "12") (pinfunction "12_12") (pintype "bidirectional"))
    )
    (net (code "78") (name "SPI1.CLK") (class "Default")
      (node (ref "P4") (pin "29") (pinfunction "29_29") (pintype "bidirectional"))
    )
    (net (code "79") (name "SPI1.CS") (class "Default")
      (node (ref "P4") (pin "31") (pinfunction "31_31") (pintype "bidirectional"))
    )
    (net (code "80") (name "SPI1.MISO") (class "Default")
      (node (ref "P4") (pin "27") (pinfunction "27_27") (pintype "bidirectional"))
    )
    (net (code "81") (name "SPI1.MOSI") (class "Default")
      (node (ref "P4") (pin "25") (pinfunction "25_25") (pintype "bidirectional"))
    )
    (net (code "82") (name "SYS_RESETN") (class "Default")
      (node (ref "B1") (pin "P9.10") (pinfunction "SYS_RESET~{N}_P9.10") (pintype "bidirectional"))
      (node (ref "U6") (pin "2") (pinfunction "A_2") (pintype "input"))
    )
    (net (code "83") (name "SYS_RESETN_5V") (class "Default")
      (node (ref "R3") (pin "2") (pinfunction "2_2") (pintype "passive"))
      (node (ref "U6") (pin "4") (pinfunction "Y_4") (pintype "output"))
      (node (ref "U7") (pin "1") (pinfunction "VEN_1") (pintype "passive"))
    )
    (net (code "84") (name "TEST") (class "Default")
      (node (ref "JP1") (pin "1") (pinfunction "1_1") (pintype "passive"))
      (node (ref "U3") (pin "17") (pinfunction "TEST/SBWTCK_17") (pintype "bidirectional"))
    )
    (net (code "85") (name "UART0.RX") (class "Default")
      (node (ref "P3") (pin "32") (pinfunction "32_32") (pintype "bidirectional"))
    )
    (net (code "86") (name "UART0.TX") (class "Default")
      (node (ref "P3") (pin "30") (pinfunction "30_30") (pintype "bidirectional"))
    )
    (net (code "87") (name "UART2_DIR") (class "Default")
      (node (ref "B1") (pin "P9.23") (pinfunction "GPIO_49_P9.23") (pintype "bidirectional"))
      (node (ref "SJ2") (pin "3") (pinfunction "3_3") (pintype "passive"))
    )
    (net (code "88") (name "UART2_RXD") (class "Default")
      (node (ref "B1") (pin "P9.22") (pinfunction "GPIO_2_P9.22") (pintype "bidirectional"))
      (node (ref "SJ3") (pin "3") (pinfunction "3_3") (pintype "passive"))
    )
    (net (code "89") (name "UART2_TXD") (class "Default")
      (node (ref "B1") (pin "P9.21") (pinfunction "GPIO_3_P9.21") (pintype "bidirectional"))
      (node (ref "SJ1") (pin "3") (pinfunction "3_3") (pintype "passive"))
    )
    (net (code "90") (name "UART4.RX") (class "Default")
      (node (ref "P4") (pin "5") (pinfunction "5_5") (pintype "bidirectional"))
    )
    (net (code "91") (name "UART4.TX") (class "Default")
      (node (ref "P4") (pin "7") (pinfunction "7_7") (pintype "bidirectional"))
    )
    (net (code "92") (name "UART_DYN_DIR") (class "Default")
      (node (ref "SJ2") (pin "2") (pinfunction "2_2") (pintype "passive"))
      (node (ref "U4") (pin "1") (pinfunction "OE_1") (pintype "input"))
      (node (ref "U5") (pin "1") (pinfunction "~{OE}_1") (pintype "input"))
    )
    (net (code "93") (name "UART_DYN_RXD") (class "Default")
      (node (ref "SJ3") (pin "2") (pinfunction "2_2") (pintype "passive"))
      (node (ref "U5") (pin "4") (pinfunction "Y_4") (pintype "output"))
    )
    (net (code "94") (name "UART_DYN_TXD") (class "Default")
      (node (ref "SJ1") (pin "2") (pinfunction "2_2") (pintype "passive"))
      (node (ref "U4") (pin "2") (pinfunction "A_2") (pintype "input"))
    )
    (net (code "95") (name "UART_MSP_DIR") (class "Default")
      (node (ref "SJ2") (pin "1") (pinfunction "1_1") (pintype "passive"))
      (node (ref "U3") (pin "8") (pinfunction "P2.0/TA1.0_8") (pintype "bidirectional"))
    )
    (net (code "96") (name "UART_MSP_RXD") (class "Default")
      (node (ref "SJ3") (pin "1") (pinfunction "1_1") (pintype "passive"))
      (node (ref "U3") (pin "3") (pinfunction "P1.1/TA0.0/UCA0RXD/UCA0SOMI/A1/CA1_3") (pintype "bidirectional"))
    )
    (net (code "97") (name "UART_MSP_TXD") (class "Default")
      (node (ref "SJ1") (pin "1") (pinfunction "1_1") (pintype "passive"))
      (node (ref "U3") (pin "4") (pinfunction "P1.2/TA0.1/UCA0TXD/UCA0SIMO/A2/CA2_4") (pintype "bidirectional"))
    )
    (net (code "98") (name "USB1.D+") (class "Default")
      (node (ref "P3") (pin "11") (pinfunction "11_11") (pintype "bidirectional"))
    )
    (net (code "99") (name "USB1.D-") (class "Default")
      (node (ref "P3") (pin "9") (pinfunction "9_9") (pintype "bidirectional"))
    )
    (net (code "100") (name "USB1.DRVVBUS") (class "Default")
      (node (ref "P3") (pin "3") (pinfunction "3_3") (pintype "bidirectional"))
    )
    (net (code "101") (name "USB1.ID") (class "Default")
      (node (ref "P3") (pin "13") (pinfunction "13_13") (pintype "bidirectional"))
    )
    (net (code "102") (name "USB1.VBUS") (class "Default")
      (node (ref "P3") (pin "5") (pinfunction "5_5") (pintype "bidirectional"))
    )
    (net (code "103") (name "USB1.VIN") (class "Default")
      (node (ref "P3") (pin "7") (pinfunction "7_7") (pintype "bidirectional"))
    )
    (net (code "104") (name "VIN") (class "Default")
      (node (ref "C8") (pin "1") (pinfunction "1_1") (pintype "passive"))
      (node (ref "D2") (pin "C") (pinfunction "C_C") (pintype "passive"))
      (node (ref "IC1") (pin "3") (pinfunction "IN_3") (pintype "input"))
      (node (ref "P3") (pin "1") (pinfunction "1_1") (pintype "bidirectional"))
    )
    (net (code "105") (name "VO") (class "Default")
      (node (ref "C9") (pin "+") (pinfunction "+_+") (pintype "passive"))
      (node (ref "D2") (pin "A") (pinfunction "A_A") (pintype "passive"))
      (node (ref "D3") (pin "C") (pinfunction "C_C") (pintype "passive"))
      (node (ref "IC1") (pin "4") (pinfunction "OUT_4") (pintype "passive"))
      (node (ref "R7") (pin "2") (pinfunction "2_2") (pintype "passive"))
    )
    (net (code "106") (name "VOUT") (class "Default")
      (node (ref "P3") (pin "24") (pinfunction "24_24") (pintype "bidirectional"))
      (node (ref "P4") (pin "13") (pinfunction "13_13") (pintype "bidirectional"))
    )
    (net (code "107") (name "XCLK") (class "Default")
      (node (ref "B1") (pin "P9.25") (pinfunction "GPIO_117_P9.25") (pintype "bidirectional"))
      (node (ref "U2") (pin "8") (pinfunction "XCLK_8") (pintype "bidirectional"))
    )
    (net (code "108") (name "unconnected-(B1A-GPIO_8-PadP8.35)") (class "Default")
      (node (ref "B1") (pin "P8.35") (pinfunction "GPIO_8_P8.35") (pintype "bidirectional"))
    )
    (net (code "109") (name "unconnected-(B1A-GPIO_9-PadP8.33)") (class "Default")
      (node (ref "B1") (pin "P8.33") (pinfunction "GPIO_9_P8.33") (pintype "bidirectional"))
    )
    (net (code "110") (name "unconnected-(B1A-GPIO_10-PadP8.31)") (class "Default")
      (node (ref "B1") (pin "P8.31") (pinfunction "GPIO_10_P8.31") (pintype "bidirectional"))
    )
    (net (code "111") (name "unconnected-(B1A-GPIO_11-PadP8.32)") (class "Default")
      (node (ref "B1") (pin "P8.32") (pinfunction "GPIO_11_P8.32") (pintype "bidirectional"))
    )
    (net (code "112") (name "unconnected-(B1A-GPIO_22-PadP8.19)") (class "Default")
      (node (ref "B1") (pin "P8.19") (pinfunction "GPIO_22_P8.19") (pintype "bidirectional"))
    )
    (net (code "113") (name "unconnected-(B1A-GPIO_23-PadP8.13)") (class "Default")
      (node (ref "B1") (pin "P8.13") (pinfunction "GPIO_23_P8.13") (pintype "bidirectional"))
    )
    (net (code "114") (name "unconnected-(B1A-GPIO_26-PadP8.14)") (class "Default")
      (node (ref "B1") (pin "P8.14") (pinfunction "GPIO_26_P8.14") (pintype "bidirectional"))
    )
    (net (code "115") (name "unconnected-(B1A-GPIO_27-PadP8.17)") (class "Default")
      (node (ref "B1") (pin "P8.17") (pinfunction "GPIO_27_P8.17") (pintype "bidirectional"))
    )
    (net (code "116") (name "unconnected-(B1A-GPIO_32-PadP8.25)") (class "Default")
      (node (ref "B1") (pin "P8.25") (pinfunction "GPIO_32_P8.25") (pintype "bidirectional"))
    )
    (net (code "117") (name "unconnected-(B1A-GPIO_33-PadP8.24)") (class "Default")
      (node (ref "B1") (pin "P8.24") (pinfunction "GPIO_33_P8.24") (pintype "bidirectional"))
    )
    (net (code "118") (name "unconnected-(B1A-GPIO_34-PadP8.5)") (class "Default")
      (node (ref "B1") (pin "P8.5") (pinfunction "GPIO_34_P8.5") (pintype "bidirectional"))
    )
    (net (code "119") (name "unconnected-(B1A-GPIO_35-PadP8.6)") (class "Default")
      (node (ref "B1") (pin "P8.6") (pinfunction "GPIO_35_P8.6") (pintype "bidirectional"))
    )
    (net (code "120") (name "unconnected-(B1A-GPIO_36-PadP8.23)") (class "Default")
      (node (ref "B1") (pin "P8.23") (pinfunction "GPIO_36_P8.23") (pintype "bidirectional"))
    )
    (net (code "121") (name "unconnected-(B1A-GPIO_37-PadP8.22)") (class "Default")
      (node (ref "B1") (pin "P8.22") (pinfunction "GPIO_37_P8.22") (pintype "bidirectional"))
    )
    (net (code "122") (name "unconnected-(B1A-GPIO_38-PadP8.3)") (class "Default")
      (node (ref "B1") (pin "P8.3") (pinfunction "GPIO_38_P8.3") (pintype "bidirectional"))
    )
    (net (code "123") (name "unconnected-(B1A-GPIO_39-PadP8.4)") (class "Default")
      (node (ref "B1") (pin "P8.4") (pinfunction "GPIO_39_P8.4") (pintype "bidirectional"))
    )
    (net (code "124") (name "unconnected-(B1A-GPIO_44-PadP8.12)") (class "Default")
      (node (ref "B1") (pin "P8.12") (pinfunction "GPIO_44_P8.12") (pintype "bidirectional"))
    )
    (net (code "125") (name "unconnected-(B1A-GPIO_45-PadP8.11)") (class "Default")
      (node (ref "B1") (pin "P8.11") (pinfunction "GPIO_45_P8.11") (pintype "bidirectional"))
    )
    (net (code "126") (name "unconnected-(B1A-GPIO_46-PadP8.16)") (class "Default")
      (node (ref "B1") (pin "P8.16") (pinfunction "GPIO_46_P8.16") (pintype "bidirectional"))
    )
    (net (code "127") (name "unconnected-(B1A-GPIO_47-PadP8.15)") (class "Default")
      (node (ref "B1") (pin "P8.15") (pinfunction "GPIO_47_P8.15") (pintype "bidirectional"))
    )
    (net (code "128") (name "unconnected-(B1A-GPIO_62-PadP8.21)") (class "Default")
      (node (ref "B1") (pin "P8.21") (pinfunction "GPIO_62_P8.21") (pintype "bidirectional"))
    )
    (net (code "129") (name "unconnected-(B1A-GPIO_63-PadP8.20)") (class "Default")
      (node (ref "B1") (pin "P8.20") (pinfunction "GPIO_63_P8.20") (pintype "bidirectional"))
    )
    (net (code "130") (name "unconnected-(B1A-GPIO_65-PadP8.18)") (class "Default")
      (node (ref "B1") (pin "P8.18") (pinfunction "GPIO_65_P8.18") (pintype "bidirectional"))
    )
    (net (code "131") (name "unconnected-(B1A-GPIO_66-PadP8.7)") (class "Default")
      (node (ref "B1") (pin "P8.7") (pinfunction "GPIO_66_P8.7") (pintype "bidirectional"))
    )
    (net (code "132") (name "unconnected-(B1A-GPIO_67-PadP8.8)") (class "Default")
      (node (ref "B1") (pin "P8.8") (pinfunction "GPIO_67_P8.8") (pintype "bidirectional"))
    )
    (net (code "133") (name "unconnected-(B1A-GPIO_68-PadP8.10)") (class "Default")
      (node (ref "B1") (pin "P8.10") (pinfunction "GPIO_68_P8.10") (pintype "bidirectional"))
    )
    (net (code "134") (name "unconnected-(B1A-GPIO_69-PadP8.9)") (class "Default")
      (node (ref "B1") (pin "P8.9") (pinfunction "GPIO_69_P8.9") (pintype "bidirectional"))
    )
    (net (code "135") (name "unconnected-(B1A-GPIO_78-PadP8.37)") (class "Default")
      (node (ref "B1") (pin "P8.37") (pinfunction "GPIO_78_P8.37") (pintype "bidirectional"))
    )
    (net (code "136") (name "unconnected-(B1A-GPIO_79-PadP8.38)") (class "Default")
      (node (ref "B1") (pin "P8.38") (pinfunction "GPIO_79_P8.38") (pintype "bidirectional"))
    )
    (net (code "137") (name "unconnected-(B1A-GPIO_80-PadP8.36)") (class "Default")
      (node (ref "B1") (pin "P8.36") (pinfunction "GPIO_80_P8.36") (pintype "bidirectional"))
    )
    (net (code "138") (name "unconnected-(B1A-GPIO_81-PadP8.34)") (class "Default")
      (node (ref "B1") (pin "P8.34") (pinfunction "GPIO_81_P8.34") (pintype "bidirectional"))
    )
    (net (code "139") (name "unconnected-(B1A-GPIO_89-PadP8.30)") (class "Default")
      (node (ref "B1") (pin "P8.30") (pinfunction "GPIO_89_P8.30") (pintype "bidirectional"))
    )
    (net (code "140") (name "unconnected-(B1B-AIN0-PadP9.39)") (class "Default")
      (node (ref "B1") (pin "P9.39") (pinfunction "AIN0_P9.39") (pintype "bidirectional"))
    )
    (net (code "141") (name "unconnected-(B1B-AIN1-PadP9.40)") (class "Default")
      (node (ref "B1") (pin "P9.40") (pinfunction "AIN1_P9.40") (pintype "bidirectional"))
    )
    (net (code "142") (name "unconnected-(B1B-AIN2-PadP9.37)") (class "Default")
      (node (ref "B1") (pin "P9.37") (pinfunction "AIN2_P9.37") (pintype "bidirectional"))
    )
    (net (code "143") (name "unconnected-(B1B-AIN3-PadP9.38)") (class "Default")
      (node (ref "B1") (pin "P9.38") (pinfunction "AIN3_P9.38") (pintype "bidirectional"))
    )
    (net (code "144") (name "unconnected-(B1B-AIN4-PadP9.33)") (class "Default")
      (node (ref "B1") (pin "P9.33") (pinfunction "AIN4_P9.33") (pintype "bidirectional"))
    )
    (net (code "145") (name "unconnected-(B1B-AIN5-PadP9.36)") (class "Default")
      (node (ref "B1") (pin "P9.36") (pinfunction "AIN5_P9.36") (pintype "bidirectional"))
    )
    (net (code "146") (name "unconnected-(B1B-AIN6-PadP9.35)") (class "Default")
      (node (ref "B1") (pin "P9.35") (pinfunction "AIN6_P9.35") (pintype "bidirectional"))
    )
    (net (code "147") (name "unconnected-(B1B-GNDA_ADC-PadP9.34)") (class "Default")
      (node (ref "B1") (pin "P9.34") (pinfunction "GNDA_ADC_P9.34") (pintype "bidirectional"))
    )
    (net (code "148") (name "unconnected-(B1B-GPIO_4-PadP9.17)") (class "Default")
      (node (ref "B1") (pin "P9.17") (pinfunction "GPIO_4_P9.17") (pintype "bidirectional"))
    )
    (net (code "149") (name "unconnected-(B1B-GPIO_5-PadP9.18)") (class "Default")
      (node (ref "B1") (pin "P9.18") (pinfunction "GPIO_5_P9.18") (pintype "bidirectional"))
    )
    (net (code "150") (name "unconnected-(B1B-GPIO_7-PadP9.42)") (class "Default")
      (node (ref "B1") (pin "P9.42") (pinfunction "GPIO_7_P9.42") (pintype "bidirectional"))
    )
    (net (code "151") (name "unconnected-(B1B-GPIO_20-PadP9.41)") (class "Default")
      (node (ref "B1") (pin "P9.41") (pinfunction "GPIO_20_P9.41") (pintype "bidirectional"))
    )
    (net (code "152") (name "unconnected-(B1B-GPIO_30-PadP9.11)") (class "Default")
      (node (ref "B1") (pin "P9.11") (pinfunction "GPIO_30_P9.11") (pintype "bidirectional"))
    )
    (net (code "153") (name "unconnected-(B1B-GPIO_31-PadP9.13)") (class "Default")
      (node (ref "B1") (pin "P9.13") (pinfunction "GPIO_31_P9.13") (pintype "bidirectional"))
    )
    (net (code "154") (name "unconnected-(B1B-GPIO_40-PadP9.14)") (class "Default")
      (node (ref "B1") (pin "P9.14") (pinfunction "GPIO_40_P9.14") (pintype "bidirectional"))
    )
    (net (code "155") (name "unconnected-(B1B-GPIO_48-PadP9.15)") (class "Default")
      (node (ref "B1") (pin "P9.15") (pinfunction "GPIO_48_P9.15") (pintype "bidirectional"))
    )
    (net (code "156") (name "unconnected-(B1B-GPIO_51-PadP9.16)") (class "Default")
      (node (ref "B1") (pin "P9.16") (pinfunction "GPIO_51_P9.16") (pintype "bidirectional"))
    )
    (net (code "157") (name "unconnected-(B1B-GPIO_60-PadP9.12)") (class "Default")
      (node (ref "B1") (pin "P9.12") (pinfunction "GPIO_60_P9.12") (pintype "bidirectional"))
    )
    (net (code "158") (name "unconnected-(B1B-GPIO_120-PadP9.31)") (class "Default")
      (node (ref "B1") (pin "P9.31") (pinfunction "GPIO_120_P9.31") (pintype "bidirectional"))
    )
    (net (code "159") (name "unconnected-(B1B-GPIO_121-PadP9.29)") (class "Default")
      (node (ref "B1") (pin "P9.29") (pinfunction "GPIO_121_P9.29") (pintype "bidirectional"))
    )
    (net (code "160") (name "unconnected-(B1B-GPIO_122-PadP9.30)") (class "Default")
      (node (ref "B1") (pin "P9.30") (pinfunction "GPIO_122_P9.30") (pintype "bidirectional"))
    )
    (net (code "161") (name "unconnected-(B1B-GPIO_123-PadP9.28)") (class "Default")
      (node (ref "B1") (pin "P9.28") (pinfunction "GPIO_123_P9.28") (pintype "bidirectional"))
    )
    (net (code "162") (name "unconnected-(B1B-GPIO_125-PadP9.27)") (class "Default")
      (node (ref "B1") (pin "P9.27") (pinfunction "GPIO_125_P9.27") (pintype "bidirectional"))
    )
    (net (code "163") (name "unconnected-(B1B-PWR_BUT-PadP9.9)") (class "Default")
      (node (ref "B1") (pin "P9.9") (pinfunction "PWR_BUT_P9.9") (pintype "bidirectional"))
    )
    (net (code "164") (name "unconnected-(B1B-SYS_5V-PadP9.7)") (class "Default")
      (node (ref "B1") (pin "P9.7") (pinfunction "SYS_5V_P9.7") (pintype "bidirectional"))
    )
    (net (code "165") (name "unconnected-(B1B-SYS_5V-PadP9.8)") (class "Default")
      (node (ref "B1") (pin "P9.8") (pinfunction "SYS_5V_P9.8") (pintype "bidirectional"))
    )
    (net (code "166") (name "unconnected-(B1B-VDD_3V3-PadP9.3)") (class "Default")
      (node (ref "B1") (pin "P9.3") (pinfunction "VDD_3V3_P9.3") (pintype "bidirectional"))
    )
    (net (code "167") (name "unconnected-(B1B-VDD_3V3-PadP9.4)") (class "Default")
      (node (ref "B1") (pin "P9.4") (pinfunction "VDD_3V3_P9.4") (pintype "bidirectional"))
    )
    (net (code "168") (name "unconnected-(B1B-VDD_ADC-PadP9.32)") (class "Default")
      (node (ref "B1") (pin "P9.32") (pinfunction "VDD_ADC_P9.32") (pintype "bidirectional"))
    )
    (net (code "169") (name "unconnected-(U1-S-Pad8)") (class "Default")
      (node (ref "U1") (pin "8") (pinfunction "S_8") (pintype "input"))
    )
    (net (code "170") (name "unconnected-(U2-DOUT0-Pad20)") (class "Default")
      (node (ref "U2") (pin "20") (pinfunction "DOUT0_20") (pintype "bidirectional"))
    )
    (net (code "171") (name "unconnected-(U2-DOUT1-Pad19)") (class "Default")
      (node (ref "U2") (pin "19") (pinfunction "DOUT1_19") (pintype "bidirectional"))
    )
    (net (code "172") (name "unconnected-(U2-RSV-Pad18)") (class "Default")
      (node (ref "U2") (pin "18") (pinfunction "RSV_18") (pintype "bidirectional"))
    )
    (net (code "173") (name "unconnected-(U3-P1.0{slash}TA0CLK{slash}ACLK{slash}A0{slash}CA0-Pad2)") (class "Default")
      (node (ref "U3") (pin "2") (pinfunction "P1.0/TA0CLK/ACLK/A0/CA0_2") (pintype "bidirectional"))
    )
    (net (code "174") (name "unconnected-(U3-P1.3{slash}ADC10CLK{slash}CAOUT{slash}VREF-{slash}VEREF-{slash}A3{slash}CA3-Pad5)") (class "Default")
      (node (ref "U3") (pin "5") (pinfunction "P1.3/ADC10CLK/CAOUT/VREF-/VEREF-/A3/CA3_5") (pintype "bidirectional"))
    )
    (net (code "175") (name "unconnected-(U3-P1.4{slash}SMCLK{slash}UCB0STE{slash}UCA0CLK{slash}VREF+{slash}VEREF+{slash}A4{slash}CA4{slash}TCK-Pad6)") (class "Default")
      (node (ref "U3") (pin "6") (pinfunction "P1.4/SMCLK/UCB0STE/UCA0CLK/VREF+/VEREF+/A4/CA4/TCK_6") (pintype "bidirectional"))
    )
    (net (code "176") (name "unconnected-(U3-P1.5{slash}TA0.0{slash}UCB0CLK{slash}UCA0STE{slash}A5{slash}CA5{slash}TMS-Pad7)") (class "Default")
      (node (ref "U3") (pin "7") (pinfunction "P1.5/TA0.0/UCB0CLK/UCA0STE/A5/CA5/TMS_7") (pintype "bidirectional"))
    )
    (net (code "177") (name "unconnected-(U3-P2.1{slash}TA1.1-Pad9)") (class "Default")
      (node (ref "U3") (pin "9") (pinfunction "P2.1/TA1.1_9") (pintype "bidirectional"))
    )
    (net (code "178") (name "unconnected-(U3-P2.2{slash}TA1.1-Pad10)") (class "Default")
      (node (ref "U3") (pin "10") (pinfunction "P2.2/TA1.1_10") (pintype "bidirectional"))
    )
    (net (code "179") (name "unconnected-(U3-P2.3{slash}TA1.0-Pad11)") (class "Default")
      (node (ref "U3") (pin "11") (pinfunction "P2.3/TA1.0_11") (pintype "bidirectional"))
    )
    (net (code "180") (name "unconnected-(U3-P2.4{slash}TA1.2-Pad12)") (class "Default")
      (node (ref "U3") (pin "12") (pinfunction "P2.4/TA1.2_12") (pintype "bidirectional"))
    )
    (net (code "181") (name "unconnected-(U3-P2.5{slash}TA1.2-Pad13)") (class "Default")
      (node (ref "U3") (pin "13") (pinfunction "P2.5/TA1.2_13") (pintype "bidirectional"))
    )
    (net (code "182") (name "unconnected-(U3-XIN{slash}P2.6{slash}TA0.1-Pad19)") (class "Default")
      (node (ref "U3") (pin "19") (pinfunction "XIN/P2.6/TA0.1_19") (pintype "bidirectional"))
    )
    (net (code "183") (name "unconnected-(U3-XOUT{slash}P2.7-Pad18)") (class "Default")
      (node (ref "U3") (pin "18") (pinfunction "XOUT/P2.7_18") (pintype "bidirectional"))
    )
    (net (code "184") (name "unconnected-(U7-NC-Pad2)") (class "Default")
      (node (ref "U7") (pin "2") (pinfunction "NC_2") (pintype "passive"))
    )
  )
)
